# Covox.net
KiCad netlist of a schematic drawn in EAGLE
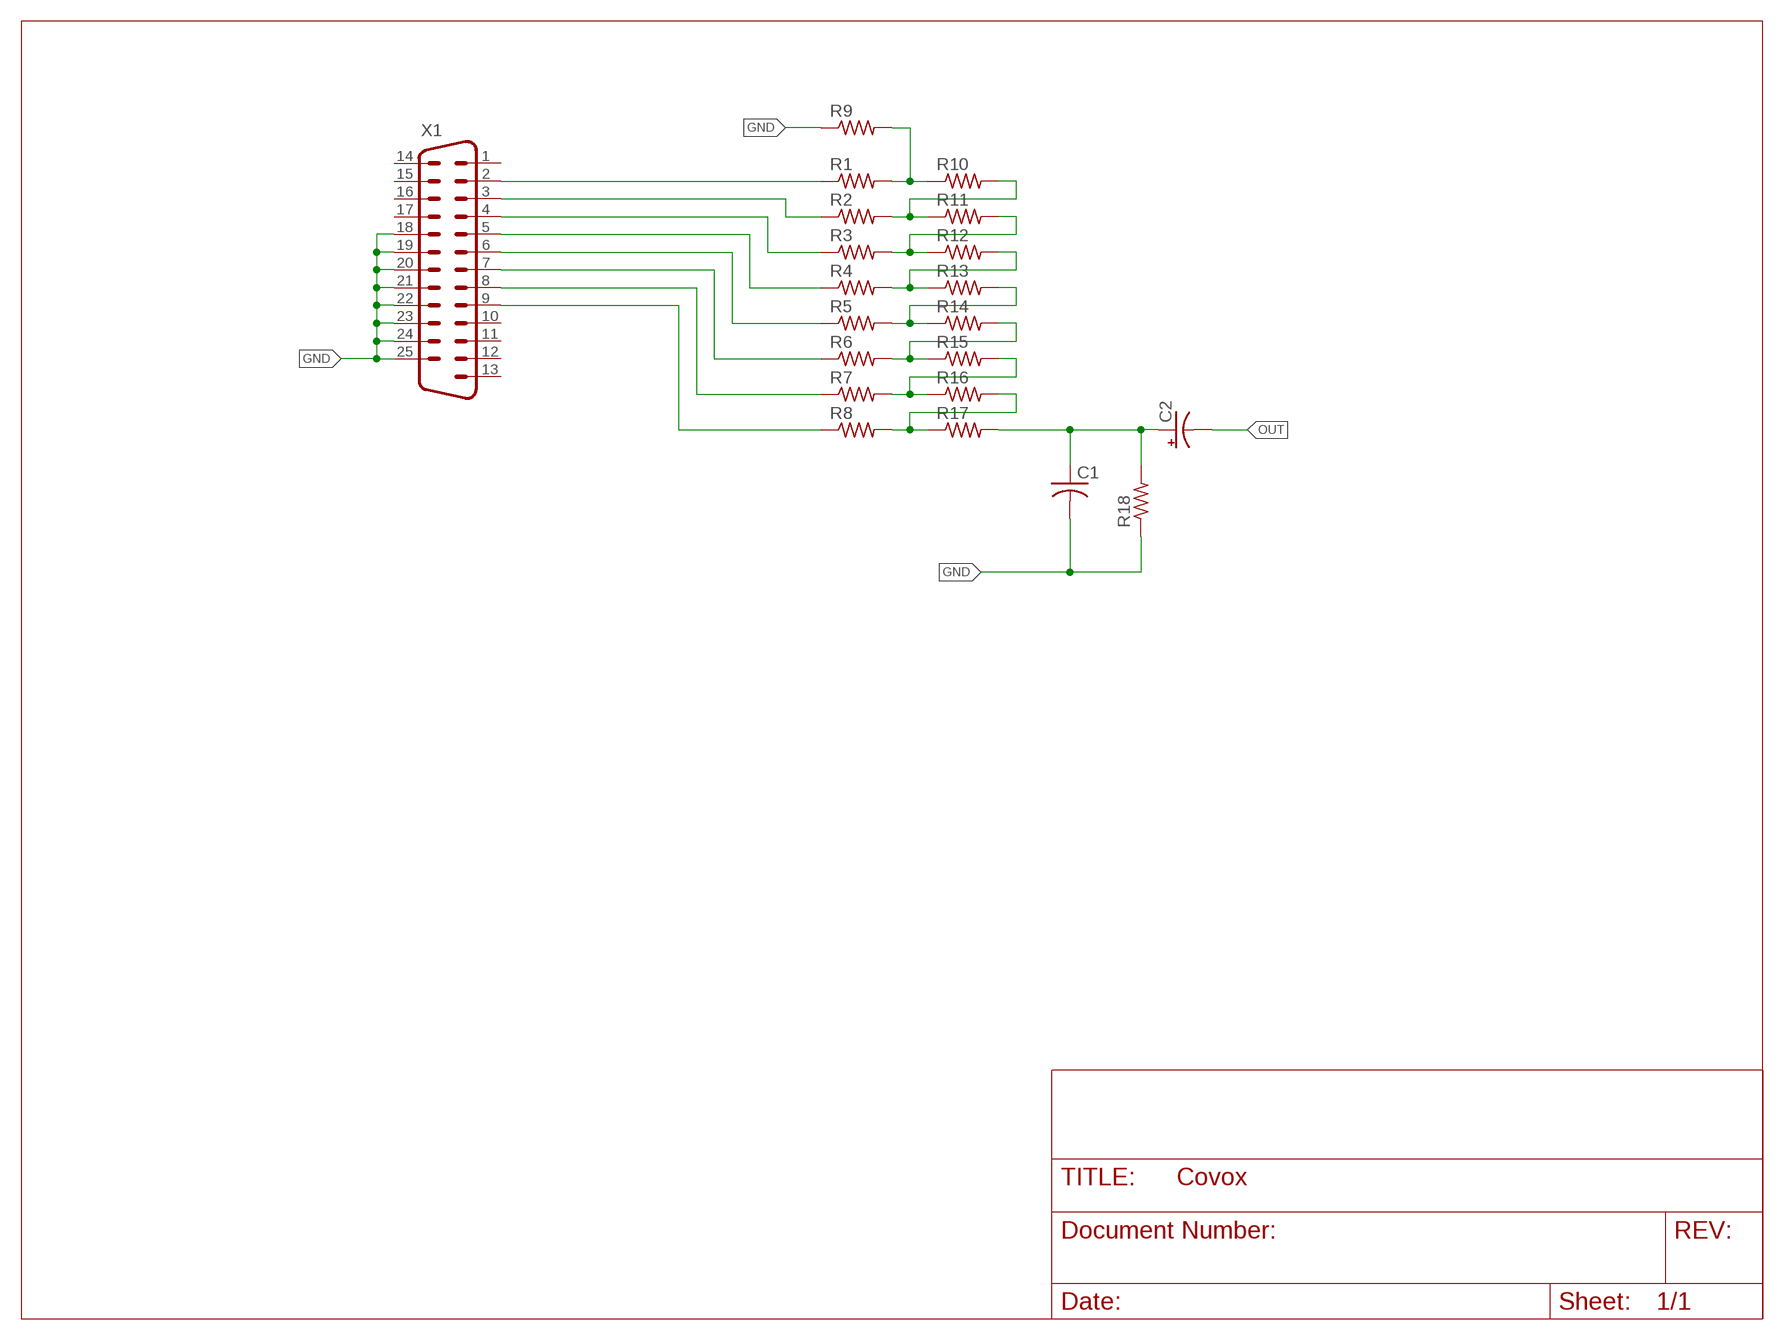
[diagram p0: schematic, sheet 1]

(export (version "E")
  (design (tool "Eeschema 10.0.6"))
  (components
    (comp (ref "C1")
      (value "C-USC0805K")
      (footprint "eagle-import:C0805K")
      (libsource (lib "eagle-import") (part "C-USC0805K"))
    )
    (comp (ref "C2")
      (value "CPOL-US153CLV-0405")
      (footprint "eagle-import:153CLV-0405")
      (libsource (lib "eagle-import") (part "CPOL-US153CLV-0405"))
    )
    (comp (ref "R1")
      (value "R-US_M0805")
      (footprint "eagle-import:M0805")
      (libsource (lib "eagle-import") (part "R-US_M0805"))
    )
    (comp (ref "R2")
      (value "R-US_M0805")
      (footprint "eagle-import:M0805")
      (libsource (lib "eagle-import") (part "R-US_M0805"))
    )
    (comp (ref "R3")
      (value "R-US_M0805")
      (footprint "eagle-import:M0805")
      (libsource (lib "eagle-import") (part "R-US_M0805"))
    )
    (comp (ref "R4")
      (value "R-US_M0805")
      (footprint "eagle-import:M0805")
      (libsource (lib "eagle-import") (part "R-US_M0805"))
    )
    (comp (ref "R5")
      (value "R-US_M0805")
      (footprint "eagle-import:M0805")
      (libsource (lib "eagle-import") (part "R-US_M0805"))
    )
    (comp (ref "R6")
      (value "R-US_M0805")
      (footprint "eagle-import:M0805")
      (libsource (lib "eagle-import") (part "R-US_M0805"))
    )
    (comp (ref "R7")
      (value "R-US_M0805")
      (footprint "eagle-import:M0805")
      (libsource (lib "eagle-import") (part "R-US_M0805"))
    )
    (comp (ref "R8")
      (value "R-US_M0805")
      (footprint "eagle-import:M0805")
      (libsource (lib "eagle-import") (part "R-US_M0805"))
    )
    (comp (ref "R9")
      (value "R-US_M0805")
      (footprint "eagle-import:M0805")
      (libsource (lib "eagle-import") (part "R-US_M0805"))
    )
    (comp (ref "R10")
      (value "R-US_M0805")
      (footprint "eagle-import:M0805")
      (libsource (lib "eagle-import") (part "R-US_M0805"))
    )
    (comp (ref "R11")
      (value "R-US_M0805")
      (footprint "eagle-import:M0805")
      (libsource (lib "eagle-import") (part "R-US_M0805"))
    )
    (comp (ref "R12")
      (value "R-US_M0805")
      (footprint "eagle-import:M0805")
      (libsource (lib "eagle-import") (part "R-US_M0805"))
    )
    (comp (ref "R13")
      (value "R-US_M0805")
      (footprint "eagle-import:M0805")
      (libsource (lib "eagle-import") (part "R-US_M0805"))
    )
    (comp (ref "R14")
      (value "R-US_M0805")
      (footprint "eagle-import:M0805")
      (libsource (lib "eagle-import") (part "R-US_M0805"))
    )
    (comp (ref "R15")
      (value "R-US_M0805")
      (footprint "eagle-import:M0805")
      (libsource (lib "eagle-import") (part "R-US_M0805"))
    )
    (comp (ref "R16")
      (value "R-US_M0805")
      (footprint "eagle-import:M0805")
      (libsource (lib "eagle-import") (part "R-US_M0805"))
    )
    (comp (ref "R17")
      (value "R-US_M0805")
      (footprint "eagle-import:M0805")
      (libsource (lib "eagle-import") (part "R-US_M0805"))
    )
    (comp (ref "R18")
      (value "R-US_M0805")
      (footprint "eagle-import:M0805")
      (libsource (lib "eagle-import") (part "R-US_M0805"))
    )
    (comp (ref "X1")
      (value "DB25D")
      (footprint "eagle-import:M25D")
      (libsource (lib "eagle-import") (part "DB25D"))
    )
  )
  (nets
    (net (code "1") (name "GND") (class "Default")
      (node (ref "C1") (pin "2") (pinfunction "2_2") (pintype "passive"))
      (node (ref "R18") (pin "1") (pinfunction "1_1") (pintype "passive"))
      (node (ref "R9") (pin "1") (pinfunction "1_1") (pintype "passive"))
      (node (ref "X1") (pin "18") (pinfunction "18_18") (pintype "passive"))
      (node (ref "X1") (pin "19") (pinfunction "19_19") (pintype "passive"))
      (node (ref "X1") (pin "20") (pinfunction "20_20") (pintype "passive"))
      (node (ref "X1") (pin "21") (pinfunction "21_21") (pintype "passive"))
      (node (ref "X1") (pin "22") (pinfunction "22_22") (pintype "passive"))
      (node (ref "X1") (pin "23") (pinfunction "23_23") (pintype "passive"))
      (node (ref "X1") (pin "24") (pinfunction "24_24") (pintype "passive"))
      (node (ref "X1") (pin "25") (pinfunction "25_25") (pintype "passive"))
    )
    (net (code "2") (name "Net-(C1-Pad1)") (class "Default")
      (node (ref "C1") (pin "1") (pinfunction "1_1") (pintype "passive"))
      (node (ref "C2") (pin "+") (pinfunction "+_+") (pintype "passive"))
      (node (ref "R17") (pin "2") (pinfunction "2_2") (pintype "passive"))
      (node (ref "R18") (pin "2") (pinfunction "2_2") (pintype "passive"))
    )
    (net (code "3") (name "Net-(R1-Pad1)") (class "Default")
      (node (ref "R1") (pin "1") (pinfunction "1_1") (pintype "passive"))
      (node (ref "X1") (pin "2") (pinfunction "2_2") (pintype "passive"))
    )
    (net (code "4") (name "Net-(R1-Pad2)") (class "Default")
      (node (ref "R1") (pin "2") (pinfunction "2_2") (pintype "passive"))
      (node (ref "R10") (pin "1") (pinfunction "1_1") (pintype "passive"))
      (node (ref "R9") (pin "2") (pinfunction "2_2") (pintype "passive"))
    )
    (net (code "5") (name "Net-(R2-Pad1)") (class "Default")
      (node (ref "R2") (pin "1") (pinfunction "1_1") (pintype "passive"))
      (node (ref "X1") (pin "3") (pinfunction "3_3") (pintype "passive"))
    )
    (net (code "6") (name "Net-(R3-Pad1)") (class "Default")
      (node (ref "R3") (pin "1") (pinfunction "1_1") (pintype "passive"))
      (node (ref "X1") (pin "4") (pinfunction "4_4") (pintype "passive"))
    )
    (net (code "7") (name "Net-(R4-Pad1)") (class "Default")
      (node (ref "R4") (pin "1") (pinfunction "1_1") (pintype "passive"))
      (node (ref "X1") (pin "5") (pinfunction "5_5") (pintype "passive"))
    )
    (net (code "8") (name "Net-(R5-Pad1)") (class "Default")
      (node (ref "R5") (pin "1") (pinfunction "1_1") (pintype "passive"))
      (node (ref "X1") (pin "6") (pinfunction "6_6") (pintype "passive"))
    )
    (net (code "9") (name "Net-(R6-Pad1)") (class "Default")
      (node (ref "R6") (pin "1") (pinfunction "1_1") (pintype "passive"))
      (node (ref "X1") (pin "7") (pinfunction "7_7") (pintype "passive"))
    )
    (net (code "10") (name "Net-(R7-Pad1)") (class "Default")
      (node (ref "R7") (pin "1") (pinfunction "1_1") (pintype "passive"))
      (node (ref "X1") (pin "8") (pinfunction "8_8") (pintype "passive"))
    )
    (net (code "11") (name "Net-(R8-Pad1)") (class "Default")
      (node (ref "R8") (pin "1") (pinfunction "1_1") (pintype "passive"))
      (node (ref "X1") (pin "9") (pinfunction "9_9") (pintype "passive"))
    )
    (net (code "12") (name "Net-(R10-Pad2)") (class "Default")
      (node (ref "R10") (pin "2") (pinfunction "2_2") (pintype "passive"))
      (node (ref "R11") (pin "1") (pinfunction "1_1") (pintype "passive"))
      (node (ref "R2") (pin "2") (pinfunction "2_2") (pintype "passive"))
    )
    (net (code "13") (name "Net-(R11-Pad2)") (class "Default")
      (node (ref "R11") (pin "2") (pinfunction "2_2") (pintype "passive"))
      (node (ref "R12") (pin "1") (pinfunction "1_1") (pintype "passive"))
      (node (ref "R3") (pin "2") (pinfunction "2_2") (pintype "passive"))
    )
    (net (code "14") (name "Net-(R12-Pad2)") (class "Default")
      (node (ref "R12") (pin "2") (pinfunction "2_2") (pintype "passive"))
      (node (ref "R13") (pin "1") (pinfunction "1_1") (pintype "passive"))
      (node (ref "R4") (pin "2") (pinfunction "2_2") (pintype "passive"))
    )
    (net (code "15") (name "Net-(R13-Pad2)") (class "Default")
      (node (ref "R13") (pin "2") (pinfunction "2_2") (pintype "passive"))
      (node (ref "R14") (pin "1") (pinfunction "1_1") (pintype "passive"))
      (node (ref "R5") (pin "2") (pinfunction "2_2") (pintype "passive"))
    )
    (net (code "16") (name "Net-(R14-Pad2)") (class "Default")
      (node (ref "R14") (pin "2") (pinfunction "2_2") (pintype "passive"))
      (node (ref "R15") (pin "1") (pinfunction "1_1") (pintype "passive"))
      (node (ref "R6") (pin "2") (pinfunction "2_2") (pintype "passive"))
    )
    (net (code "17") (name "Net-(R15-Pad2)") (class "Default")
      (node (ref "R15") (pin "2") (pinfunction "2_2") (pintype "passive"))
      (node (ref "R16") (pin "1") (pinfunction "1_1") (pintype "passive"))
      (node (ref "R7") (pin "2") (pinfunction "2_2") (pintype "passive"))
    )
    (net (code "18") (name "Net-(R16-Pad2)") (class "Default")
      (node (ref "R16") (pin "2") (pinfunction "2_2") (pintype "passive"))
      (node (ref "R17") (pin "1") (pinfunction "1_1") (pintype "passive"))
      (node (ref "R8") (pin "2") (pinfunction "2_2") (pintype "passive"))
    )
    (net (code "19") (name "OUT") (class "Default")
      (node (ref "C2") (pin "-") (pinfunction "-_-") (pintype "passive"))
    )
    (net (code "20") (name "unconnected-(X1-Pad1)") (class "Default")
      (node (ref "X1") (pin "1") (pinfunction "1_1") (pintype "passive"))
    )
    (net (code "21") (name "unconnected-(X1-Pad10)") (class "Default")
      (node (ref "X1") (pin "10") (pinfunction "10_10") (pintype "passive"))
    )
    (net (code "22") (name "unconnected-(X1-Pad11)") (class "Default")
      (node (ref "X1") (pin "11") (pinfunction "11_11") (pintype "passive"))
    )
    (net (code "23") (name "unconnected-(X1-Pad12)") (class "Default")
      (node (ref "X1") (pin "12") (pinfunction "12_12") (pintype "passive"))
    )
    (net (code "24") (name "unconnected-(X1-Pad13)") (class "Default")
      (node (ref "X1") (pin "13") (pinfunction "13_13") (pintype "passive"))
    )
    (net (code "25") (name "unconnected-(X1-Pad14)") (class "Default")
      (node (ref "X1") (pin "14") (pinfunction "14_14") (pintype "passive"))
    )
    (net (code "26") (name "unconnected-(X1-Pad15)") (class "Default")
      (node (ref "X1") (pin "15") (pinfunction "15_15") (pintype "passive"))
    )
    (net (code "27") (name "unconnected-(X1-Pad16)") (class "Default")
      (node (ref "X1") (pin "16") (pinfunction "16_16") (pintype "passive"))
    )
    (net (code "28") (name "unconnected-(X1-Pad17)") (class "Default")
      (node (ref "X1") (pin "17") (pinfunction "17_17") (pintype "passive"))
    )
  )
)
